# PMU.net
KiCad netlist of a schematic drawn in Altium Designer
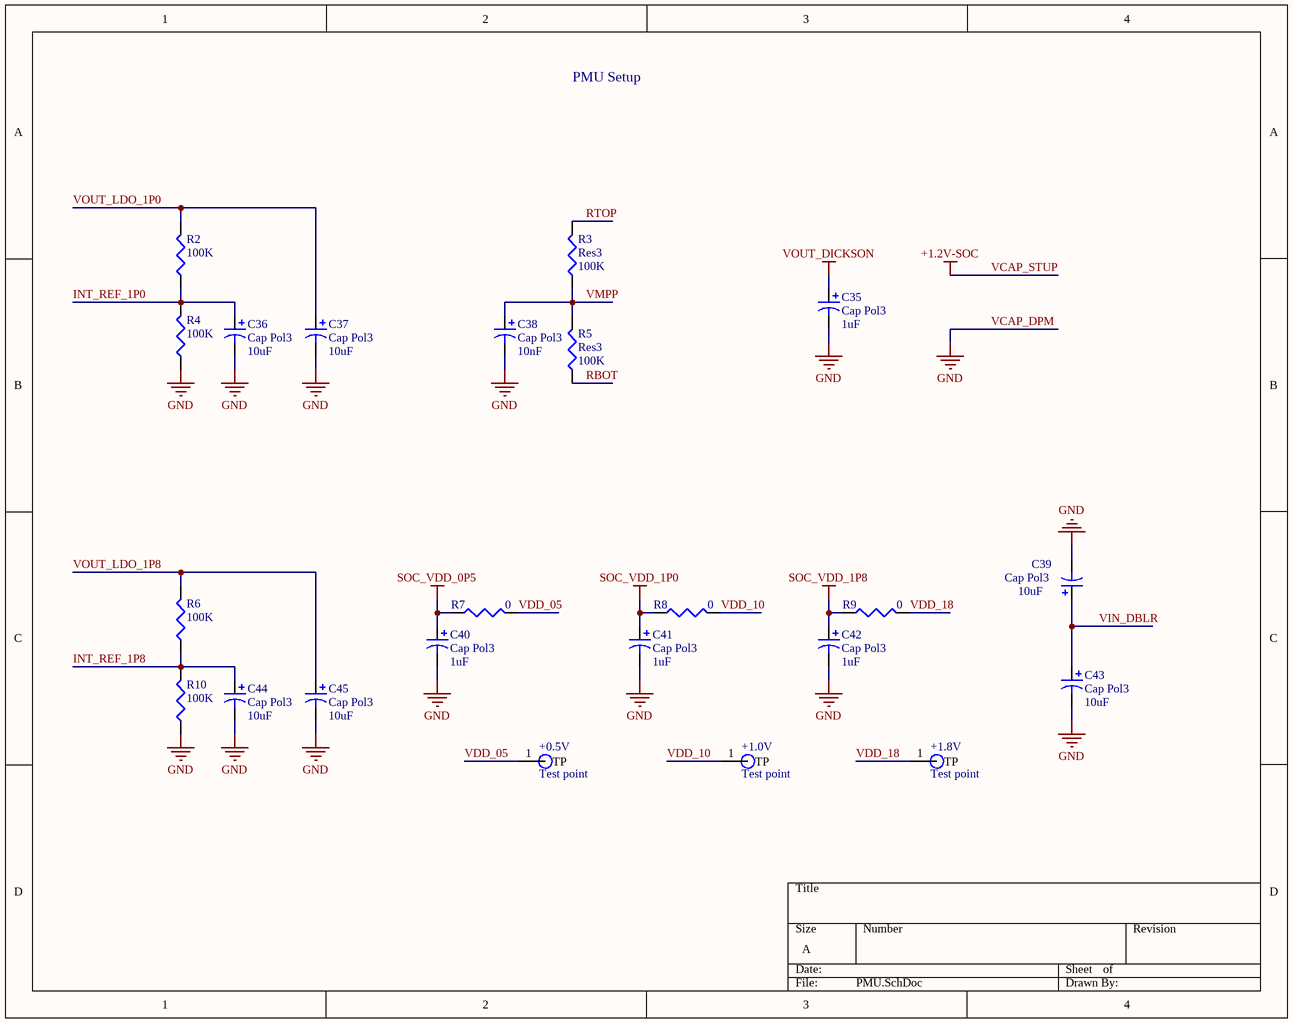
[diagram p0: PMU.SchDoc]

(export (version "E")
  (design (tool "Eeschema 10.0.6"))
  (components
    (comp (ref "+0.5V") (value "Test point") (footprint "TP") (libsource (lib "INERTIA") (part "Test point")))
    (comp (ref "+1.0V") (value "Test point") (footprint "TP") (libsource (lib "INERTIA") (part "Test point")))
    (comp (ref "+1.8V") (value "Test point") (footprint "TP") (libsource (lib "INERTIA") (part "Test point")))
    (comp (ref "C35")
      (value "Cap Pol3")
      (footprint "0402")
      (description "Polarized Capacitor (Surface Mount)")
      (fields (field (name "ALTIUM_VALUE") "1uF") (field (name "PUBLISHER") "Altium Limited"))
      (libsource (lib "Miscellaneous Devices") (part "Cap Pol3"))
    )
    (comp (ref "C36")
      (value "Cap Pol3")
      (footprint "0402")
      (description "Polarized Capacitor (Surface Mount)")
      (fields (field (name "ALTIUM_VALUE") "10uF") (field (name "PUBLISHER") "Altium Limited"))
      (libsource (lib "Miscellaneous Devices") (part "Cap Pol3"))
    )
    (comp (ref "C37")
      (value "Cap Pol3")
      (footprint "0402")
      (description "Polarized Capacitor (Surface Mount)")
      (fields (field (name "ALTIUM_VALUE") "10uF") (field (name "PUBLISHER") "Altium Limited"))
      (libsource (lib "Miscellaneous Devices") (part "Cap Pol3"))
    )
    (comp (ref "C38")
      (value "Cap Pol3")
      (footprint "0402")
      (description "Polarized Capacitor (Surface Mount)")
      (fields (field (name "ALTIUM_VALUE") "10nF") (field (name "PUBLISHER") "Altium Limited"))
      (libsource (lib "Miscellaneous Devices") (part "Cap Pol3"))
    )
    (comp (ref "C39")
      (value "Cap Pol3")
      (footprint "0402")
      (description "Polarized Capacitor (Surface Mount)")
      (fields (field (name "ALTIUM_VALUE") "10uF") (field (name "PUBLISHER") "Altium Limited"))
      (libsource (lib "Miscellaneous Devices") (part "Cap Pol3"))
    )
    (comp (ref "C40")
      (value "Cap Pol3")
      (footprint "0402")
      (description "Polarized Capacitor (Surface Mount)")
      (fields (field (name "ALTIUM_VALUE") "1uF") (field (name "PUBLISHER") "Altium Limited"))
      (libsource (lib "Miscellaneous Devices") (part "Cap Pol3"))
    )
    (comp (ref "C41")
      (value "Cap Pol3")
      (footprint "0402")
      (description "Polarized Capacitor (Surface Mount)")
      (fields (field (name "ALTIUM_VALUE") "1uF") (field (name "PUBLISHER") "Altium Limited"))
      (libsource (lib "Miscellaneous Devices") (part "Cap Pol3"))
    )
    (comp (ref "C42")
      (value "Cap Pol3")
      (footprint "0402")
      (description "Polarized Capacitor (Surface Mount)")
      (fields (field (name "ALTIUM_VALUE") "1uF") (field (name "PUBLISHER") "Altium Limited"))
      (libsource (lib "Miscellaneous Devices") (part "Cap Pol3"))
    )
    (comp (ref "C43")
      (value "Cap Pol3")
      (footprint "0402")
      (description "Polarized Capacitor (Surface Mount)")
      (fields (field (name "ALTIUM_VALUE") "10uF") (field (name "PUBLISHER") "Altium Limited"))
      (libsource (lib "Miscellaneous Devices") (part "Cap Pol3"))
    )
    (comp (ref "C44")
      (value "Cap Pol3")
      (footprint "0402")
      (description "Polarized Capacitor (Surface Mount)")
      (fields (field (name "ALTIUM_VALUE") "10uF") (field (name "PUBLISHER") "Altium Limited"))
      (libsource (lib "Miscellaneous Devices") (part "Cap Pol3"))
    )
    (comp (ref "C45")
      (value "Cap Pol3")
      (footprint "0402")
      (description "Polarized Capacitor (Surface Mount)")
      (fields (field (name "ALTIUM_VALUE") "10uF") (field (name "PUBLISHER") "Altium Limited"))
      (libsource (lib "Miscellaneous Devices") (part "Cap Pol3"))
    )
    (comp (ref "R2")
      (value "100K")
      (footprint "0402")
      (description "Resistor")
      (fields (field (name "Comment") "Res3") (field (name "PUBLISHER") "Altium Limited"))
      (libsource (lib "Miscellaneous Devices") (part "Res3"))
    )
    (comp (ref "R3")
      (value "Res3")
      (footprint "0402")
      (description "Resistor")
      (fields (field (name "ALTIUM_VALUE") "100K") (field (name "PUBLISHER") "Altium Limited"))
      (libsource (lib "Miscellaneous Devices") (part "Res3"))
    )
    (comp (ref "R4")
      (value "100K")
      (footprint "0402")
      (description "Resistor")
      (fields (field (name "Comment") "Res3") (field (name "PUBLISHER") "Altium Limited"))
      (libsource (lib "Miscellaneous Devices") (part "Res3"))
    )
    (comp (ref "R5")
      (value "Res3")
      (footprint "0402")
      (description "Resistor")
      (fields (field (name "ALTIUM_VALUE") "100K") (field (name "PUBLISHER") "Altium Limited"))
      (libsource (lib "Miscellaneous Devices") (part "Res3"))
    )
    (comp (ref "R6")
      (value "100K")
      (footprint "0402")
      (description "Resistor")
      (fields (field (name "Comment") "Res3") (field (name "PUBLISHER") "Altium Limited"))
      (libsource (lib "Miscellaneous Devices") (part "Res3"))
    )
    (comp (ref "R7")
      (value "0")
      (footprint "0402")
      (description "Resistor")
      (fields (field (name "Comment") "Res3") (field (name "PUBLISHER") "Altium Limited"))
      (libsource (lib "Miscellaneous Devices") (part "Res3"))
    )
    (comp (ref "R8")
      (value "0")
      (footprint "0402")
      (description "Resistor")
      (fields (field (name "Comment") "Res3") (field (name "PUBLISHER") "Altium Limited"))
      (libsource (lib "Miscellaneous Devices") (part "Res3"))
    )
    (comp (ref "R9")
      (value "0")
      (footprint "0402")
      (description "Resistor")
      (fields (field (name "Comment") "Res3") (field (name "PUBLISHER") "Altium Limited"))
      (libsource (lib "Miscellaneous Devices") (part "Res3"))
    )
    (comp (ref "R10")
      (value "100K")
      (footprint "0402")
      (description "Resistor")
      (fields (field (name "Comment") "Res3") (field (name "PUBLISHER") "Altium Limited"))
      (libsource (lib "Miscellaneous Devices") (part "Res3"))
    )
  )
  (nets
    (net (code "2") (name "/INT_REF_1P0") (class "Default")
      (node (ref "C36") (pin "1") (pinfunction "1_1") (pintype "passive"))
      (node (ref "R2") (pin "1") (pinfunction "1_1") (pintype "passive"))
      (node (ref "R4") (pin "2") (pinfunction "2_2") (pintype "passive"))
    )
    (net (code "3") (name "/INT_REF_1P8") (class "Default")
      (node (ref "C44") (pin "1") (pinfunction "1_1") (pintype "passive"))
      (node (ref "R10") (pin "2") (pinfunction "2_2") (pintype "passive"))
      (node (ref "R6") (pin "1") (pinfunction "1_1") (pintype "passive"))
    )
    (net (code "4") (name "/RBOT") (class "Default")
      (node (ref "R5") (pin "1") (pinfunction "1_1") (pintype "passive"))
    )
    (net (code "5") (name "/RTOP") (class "Default")
      (node (ref "R3") (pin "2") (pinfunction "2_2") (pintype "passive"))
    )
    (net (code "6") (name "/VDD_05") (class "Default")
      (node (ref "+0.5V") (pin "1") (pinfunction "TP_1") (pintype "passive"))
      (node (ref "R7") (pin "2") (pinfunction "2_2") (pintype "passive"))
    )
    (net (code "7") (name "/VDD_10") (class "Default")
      (node (ref "+1.0V") (pin "1") (pinfunction "TP_1") (pintype "passive"))
      (node (ref "R8") (pin "2") (pinfunction "2_2") (pintype "passive"))
    )
    (net (code "8") (name "/VDD_18") (class "Default")
      (node (ref "+1.8V") (pin "1") (pinfunction "TP_1") (pintype "passive"))
      (node (ref "R9") (pin "2") (pinfunction "2_2") (pintype "passive"))
    )
    (net (code "9") (name "/VIN_DBLR") (class "Default")
      (node (ref "C39") (pin "1") (pinfunction "1_1") (pintype "passive"))
      (node (ref "C43") (pin "1") (pinfunction "1_1") (pintype "passive"))
    )
    (net (code "10") (name "/VMPP") (class "Default")
      (node (ref "C38") (pin "1") (pinfunction "1_1") (pintype "passive"))
      (node (ref "R3") (pin "1") (pinfunction "1_1") (pintype "passive"))
      (node (ref "R5") (pin "2") (pinfunction "2_2") (pintype "passive"))
    )
    (net (code "11") (name "/VOUT_LDO_1P0") (class "Default")
      (node (ref "C37") (pin "1") (pinfunction "1_1") (pintype "passive"))
      (node (ref "R2") (pin "2") (pinfunction "2_2") (pintype "passive"))
    )
    (net (code "12") (name "/VOUT_LDO_1P8") (class "Default")
      (node (ref "C45") (pin "1") (pinfunction "1_1") (pintype "passive"))
      (node (ref "R6") (pin "2") (pinfunction "2_2") (pintype "passive"))
    )
    (net (code "13") (name "GND") (class "Default")
      (node (ref "C35") (pin "2") (pinfunction "2_2") (pintype "passive"))
      (node (ref "C36") (pin "2") (pinfunction "2_2") (pintype "passive"))
      (node (ref "C37") (pin "2") (pinfunction "2_2") (pintype "passive"))
      (node (ref "C38") (pin "2") (pinfunction "2_2") (pintype "passive"))
      (node (ref "C39") (pin "2") (pinfunction "2_2") (pintype "passive"))
      (node (ref "C40") (pin "2") (pinfunction "2_2") (pintype "passive"))
      (node (ref "C41") (pin "2") (pinfunction "2_2") (pintype "passive"))
      (node (ref "C42") (pin "2") (pinfunction "2_2") (pintype "passive"))
      (node (ref "C43") (pin "2") (pinfunction "2_2") (pintype "passive"))
      (node (ref "C44") (pin "2") (pinfunction "2_2") (pintype "passive"))
      (node (ref "C45") (pin "2") (pinfunction "2_2") (pintype "passive"))
      (node (ref "R10") (pin "1") (pinfunction "1_1") (pintype "passive"))
      (node (ref "R4") (pin "1") (pinfunction "1_1") (pintype "passive"))
    )
    (net (code "14") (name "SOC_VDD_0P5") (class "Default")
      (node (ref "C40") (pin "1") (pinfunction "1_1") (pintype "passive"))
      (node (ref "R7") (pin "1") (pinfunction "1_1") (pintype "passive"))
    )
    (net (code "15") (name "SOC_VDD_1P0") (class "Default")
      (node (ref "C41") (pin "1") (pinfunction "1_1") (pintype "passive"))
      (node (ref "R8") (pin "1") (pinfunction "1_1") (pintype "passive"))
    )
    (net (code "16") (name "SOC_VDD_1P8") (class "Default")
      (node (ref "C42") (pin "1") (pinfunction "1_1") (pintype "passive"))
      (node (ref "R9") (pin "1") (pinfunction "1_1") (pintype "passive"))
    )
    (net (code "17") (name "VOUT_DICKSON") (class "Default")
      (node (ref "C35") (pin "1") (pinfunction "1_1") (pintype "passive"))
    )
  )
)
